# UhOh-v11.net
KiCad netlist of a schematic drawn in EAGLE
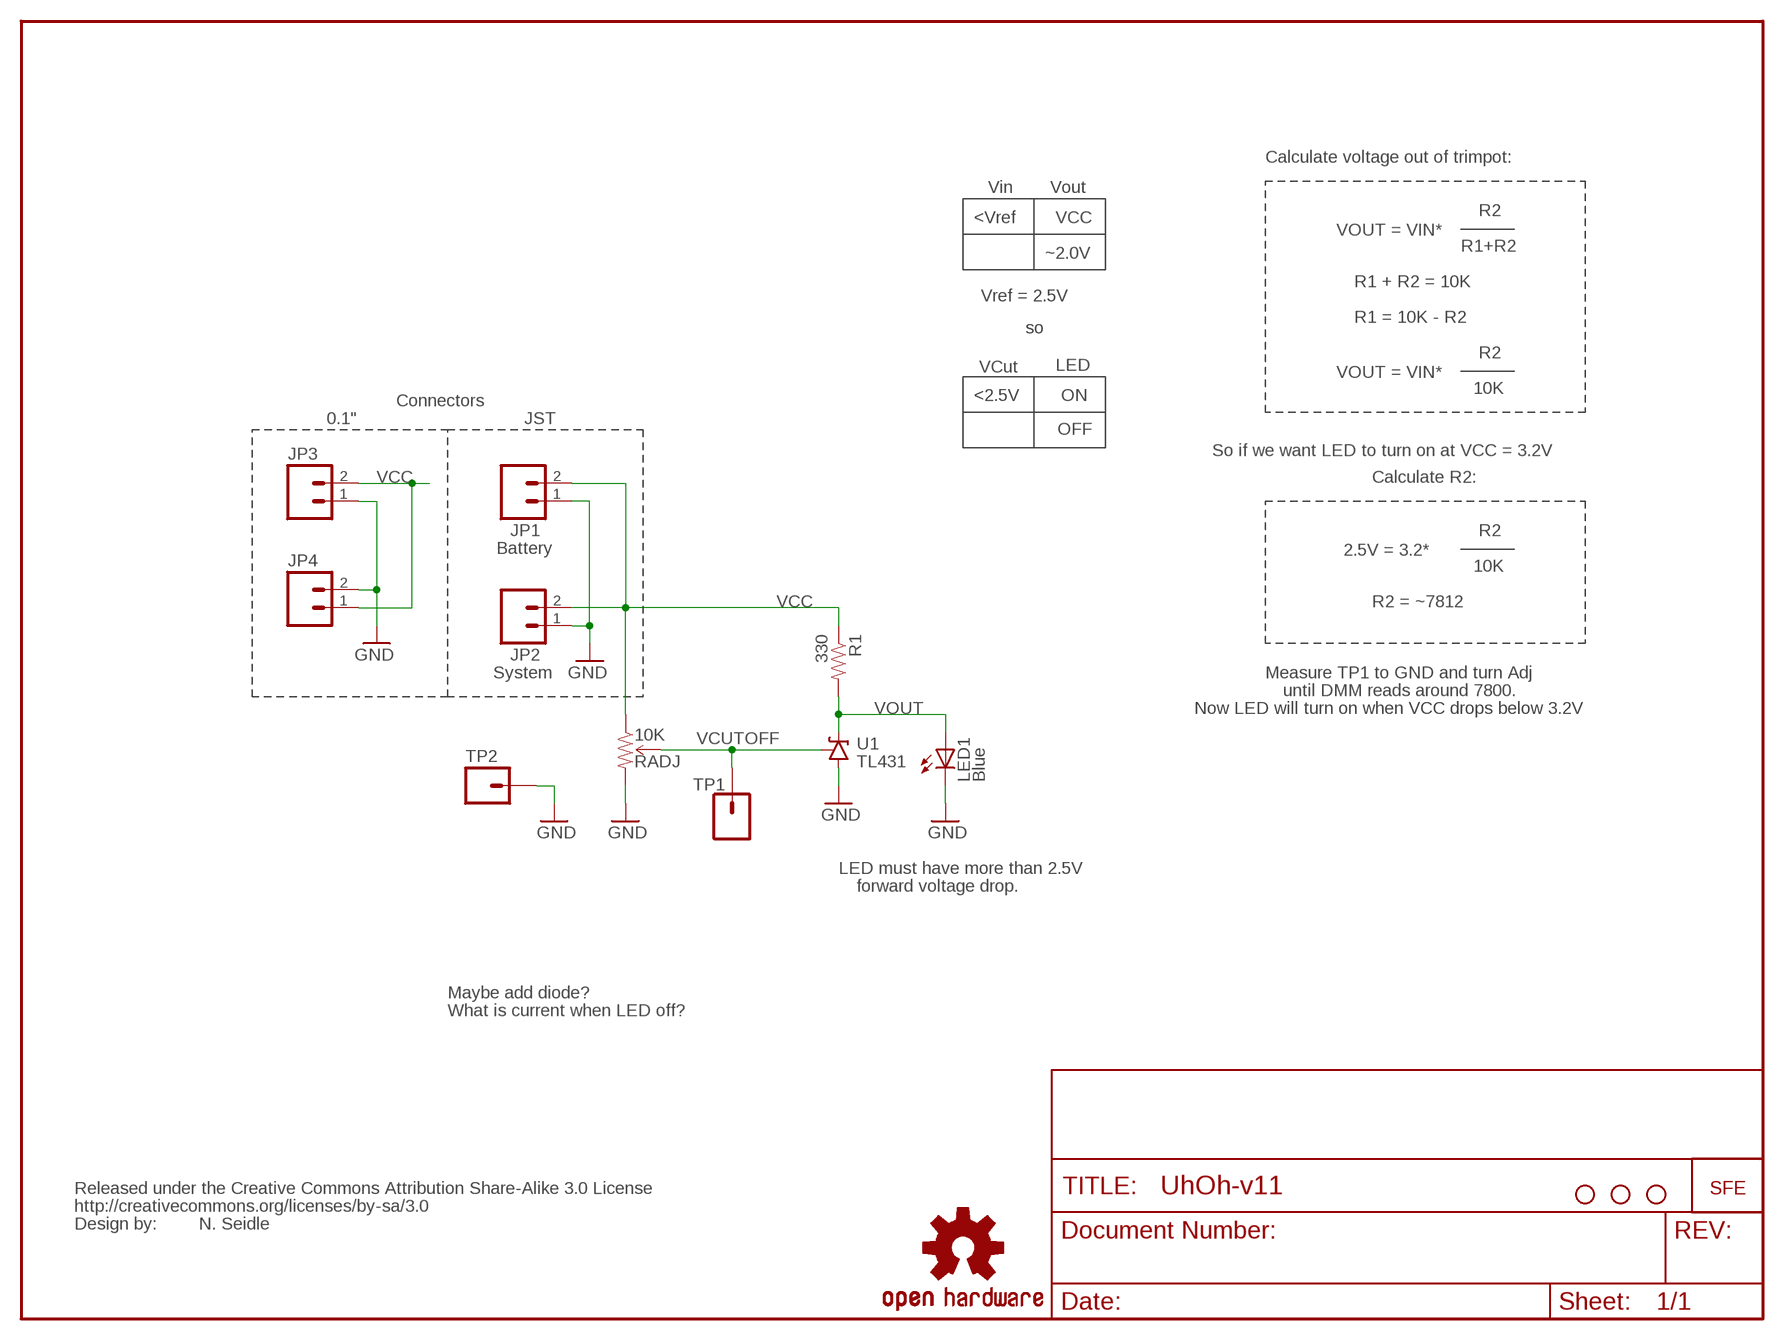
[diagram p0: schematic, sheet 1]

(export (version "E")
  (design (tool "Eeschema 10.0.6"))
  (components
    (comp (ref "JP1")
      (value "Battery")
      (footprint "eagle-import:JST-2-PTH")
      (libsource (lib "eagle-import") (part "M02JST-PTH-2"))
    )
    (comp (ref "JP2")
      (value "System")
      (footprint "eagle-import:JST-2-PTH")
      (libsource (lib "eagle-import") (part "M02JST-PTH-2"))
    )
    (comp (ref "JP3")
      (value "M02PTH")
      (footprint "eagle-import:1X02")
      (libsource (lib "eagle-import") (part "M02PTH"))
    )
    (comp (ref "JP4")
      (value "M02PTH")
      (footprint "eagle-import:1X02")
      (libsource (lib "eagle-import") (part "M02PTH"))
    )
    (comp (ref "JP31")
      (value "STAND-OFF")
      (footprint "eagle-import:STAND-OFF")
      (libsource (lib "eagle-import") (part "STAND-OFF"))
    )
    (comp (ref "JP41")
      (value "STAND-OFF")
      (footprint "eagle-import:STAND-OFF")
      (libsource (lib "eagle-import") (part "STAND-OFF"))
    )
    (comp (ref "JP51")
      (value "LOGO-SFENEW")
      (footprint "eagle-import:SFE-NEW-WEBLOGO")
      (libsource (lib "eagle-import") (part "LOGO-SFENEW"))
    )
    (comp (ref "JP61")
      (value "STAND-OFF")
      (footprint "eagle-import:STAND-OFF")
      (libsource (lib "eagle-import") (part "STAND-OFF"))
    )
    (comp (ref "LED1")
      (value "Blue")
      (footprint "eagle-import:LED10MM-2")
      (libsource (lib "eagle-import") (part "LED10MM2"))
    )
    (comp (ref "R1")
      (value "330")
      (footprint "eagle-import:AXIAL-0.3")
      (libsource (lib "eagle-import") (part "RESISTORAXIAL-0.3"))
    )
    (comp (ref "RADJ")
      (value "10K")
      (footprint "eagle-import:3386U")
      (libsource (lib "eagle-import") (part "TRIMPOT-PTH-KNOB"))
    )
    (comp (ref "TP1")
      (value "TP1")
      (footprint "eagle-import:1X01")
      (libsource (lib "eagle-import") (part "M01PTH"))
    )
    (comp (ref "TP2")
      (value "TP2")
      (footprint "eagle-import:1X01")
      (libsource (lib "eagle-import") (part "M01PTH"))
    )
    (comp (ref "U$1")
      (value "OSHW-LOGOS")
      (footprint "eagle-import:OSHW-LOGO-S")
      (libsource (lib "eagle-import") (part "OSHW-LOGOS"))
    )
    (comp (ref "U$2")
      (value "CREATIVE_COMMONS")
      (footprint "eagle-import:CREATIVE_COMMONS")
      (libsource (lib "eagle-import") (part "CREATIVE_COMMONS"))
    )
    (comp (ref "U1")
      (value "TL431")
      (footprint "eagle-import:TO-92")
      (libsource (lib "eagle-import") (part "TL431PTH"))
    )
  )
  (nets
    (net (code "1") (name "/VCC") (class "Default")
      (node (ref "JP1") (pin "2") (pinfunction "2_2") (pintype "passive"))
      (node (ref "JP2") (pin "2") (pinfunction "2_2") (pintype "passive"))
      (node (ref "JP3") (pin "2") (pinfunction "2_2") (pintype "passive"))
      (node (ref "JP4") (pin "1") (pinfunction "1_1") (pintype "passive"))
      (node (ref "R1") (pin "P$1") (pinfunction "1_P$1") (pintype "passive"))
      (node (ref "RADJ") (pin "1") (pinfunction "CCW_1") (pintype "passive"))
    )
    (net (code "2") (name "/VCUTOFF") (class "Default")
      (node (ref "RADJ") (pin "2") (pinfunction "WIPER_2") (pintype "passive"))
      (node (ref "TP1") (pin "1") (pinfunction "1_1") (pintype "passive"))
      (node (ref "U1") (pin "1") (pinfunction "R_1") (pintype "bidirectional"))
    )
    (net (code "3") (name "/VOUT") (class "Default")
      (node (ref "LED1") (pin "A") (pinfunction "A_A") (pintype "passive"))
      (node (ref "R1") (pin "P$2") (pinfunction "2_P$2") (pintype "passive"))
      (node (ref "U1") (pin "3") (pinfunction "C_3") (pintype "passive"))
    )
    (net (code "4") (name "GND") (class "Default")
      (node (ref "JP1") (pin "1") (pinfunction "1_1") (pintype "passive"))
      (node (ref "JP2") (pin "1") (pinfunction "1_1") (pintype "passive"))
      (node (ref "JP3") (pin "1") (pinfunction "1_1") (pintype "passive"))
      (node (ref "JP4") (pin "2") (pinfunction "2_2") (pintype "passive"))
      (node (ref "LED1") (pin "K") (pinfunction "C_K") (pintype "passive"))
      (node (ref "RADJ") (pin "3") (pinfunction "CW_3") (pintype "passive"))
      (node (ref "TP2") (pin "1") (pinfunction "1_1") (pintype "passive"))
      (node (ref "U1") (pin "2") (pinfunction "A_2") (pintype "passive"))
    )
  )
)
